# MAIN-SCH.net
KiCad netlist of a schematic drawn in Altium Designer
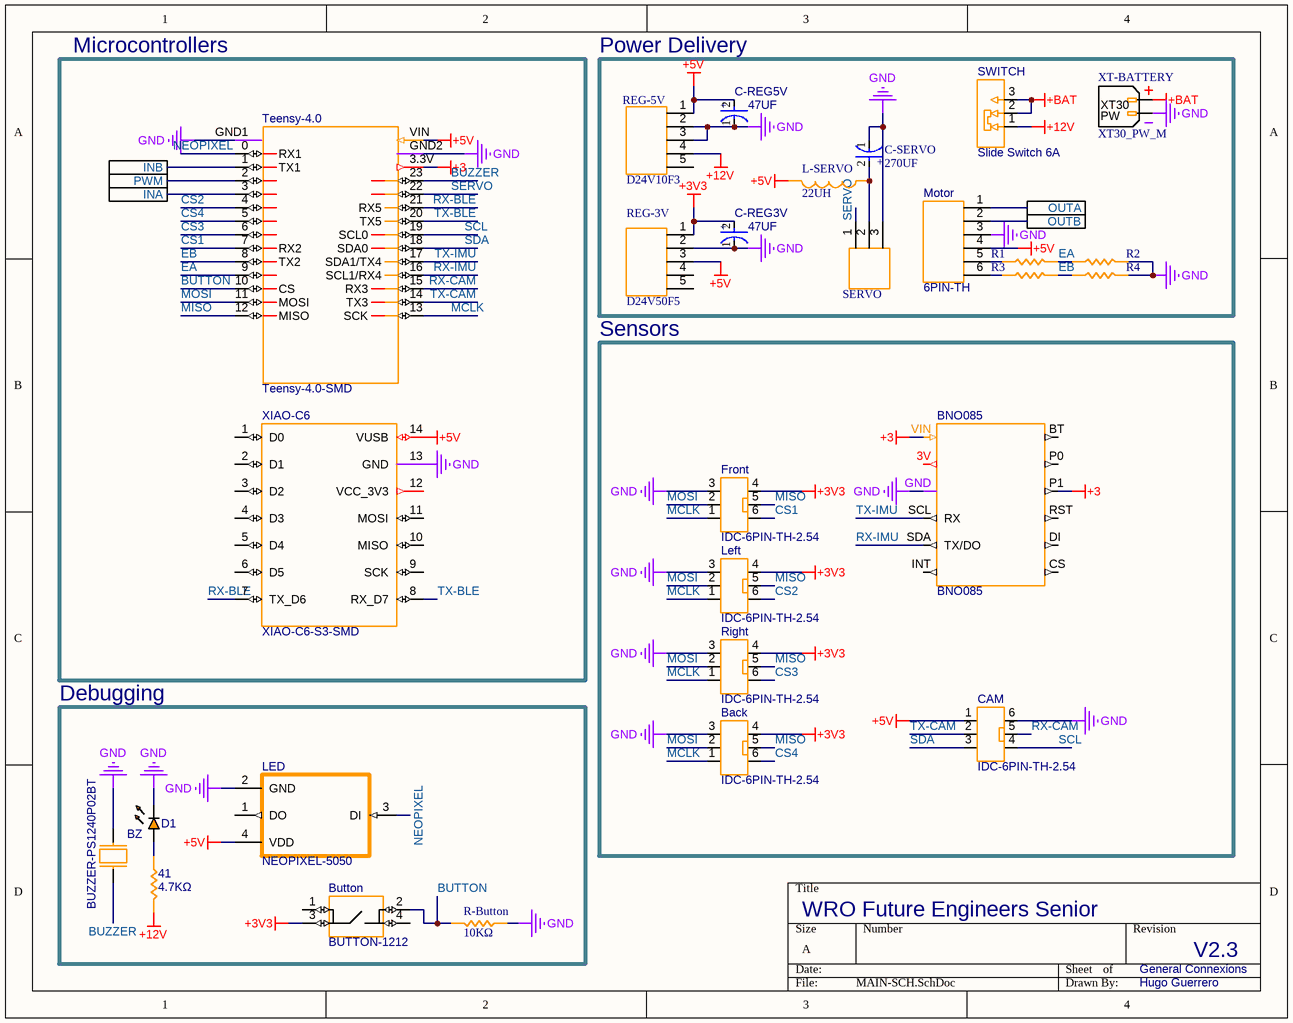
[diagram p0: MAIN-SCH.SchDoc]

(export (version "E")
  (design (tool "Eeschema 10.0.6"))
  (components
    (comp (ref "41")
      (value "4.7KΩ")
      (footprint "RES_0603")
      (description "Resistor SMD 0603 generic")
      (libsource (lib "GenericRC") (part "RES_0603"))
    )
    (comp (ref "Back")
      (value "IDC-6PIN-TH-2.54")
      (footprint "IDC-6PIN-TH-2.54")
      (libsource (lib "") (part "IDC-6PIN-TH-2.54_1"))
    )
    (comp (ref "BNO085") (value "BNO085") (footprint "BNO085") (libsource (lib "RC") (part "BNO085")))
    (comp (ref "Button") (value "BUTTON-1212") (footprint "BUTTON") (libsource (lib "RC") (part "BUTTON")))
    (comp (ref "BZ")
      (value "BUZZER-PS1240P02BT")
      (footprint "BUZZER")
      (libsource (lib "RC") (part "BUZZER-PS1240P02BT"))
    )
    (comp (ref "C-REG3V")
      (value "47UF")
      (footprint "FP-FTD8-MFG")
      (description "CAP ALUM 220UF 20% 25V SMD")
      (fields (field (name "TOLERANCE") "20%") (field (name "VOLTAGE") "25V"))
      (libsource (lib "Altium Content Vault") (part "cf48714ba7e38822c1575c7ec0b6d1f"))
    )
    (comp (ref "C-REG5V")
      (value "47UF")
      (footprint "FP-FTD8-MFG")
      (description "CAP ALUM 220UF 20% 25V SMD")
      (fields (field (name "TOLERANCE") "20%") (field (name "VOLTAGE") "25V"))
      (libsource (lib "Altium Content Vault") (part "cf48714ba7e38822c1575c7ec0b6d1f"))
    )
    (comp (ref "C-SERVO")
      (value "270UF")
      (footprint "FP-FTD8-MFG")
      (description "CAP ALUM 220UF 20% 25V SMD")
      (fields (field (name "TOLERANCE") "20%") (field (name "VOLTAGE") "25V"))
      (libsource (lib "Altium Content Vault") (part "cf48714ba7e38822c1575c7ec0b6d1f"))
    )
    (comp (ref "CAM")
      (value "IDC-6PIN-TH-2.54")
      (footprint "IDC-6PIN-TH-2.54")
      (libsource (lib "RC") (part "IDC-6PIN-TH-2.54"))
    )
    (comp (ref "D1")
      (value "LED_0603")
      (footprint "LED_0603")
      (libsource (lib "GenericRC") (part "LED_0603"))
    )
    (comp (ref "D24V10F3")
      (value "REG-5V")
      (footprint "5PIN-TH")
      (description "2.54 Header")
      (libsource (lib "RC") (part "5PIN-TH"))
    )
    (comp (ref "D24V50F5")
      (value "REG-3V")
      (footprint "5PIN-TH")
      (description "2.54 Header")
      (libsource (lib "RC") (part "5PIN-TH"))
    )
    (comp (ref "Front")
      (value "IDC-6PIN-TH-2.54")
      (footprint "IDC-6PIN-TH-2.54")
      (libsource (lib "") (part "IDC-6PIN-TH-2.54_1"))
    )
    (comp (ref "L-SERVO")
      (value "22UH")
      (footprint "WRO-INDUCTOR")
      (description "Voltage Boost Inductor")
      (libsource (lib "RC") (part "WRO-INDUCTOR"))
    )
    (comp (ref "LED")
      (value "NEOPIXEL-5050")
      (footprint "NEOPIXEL-5050")
      (libsource (lib "RC") (part "NEOPIXEL-5050"))
    )
    (comp (ref "Left")
      (value "IDC-6PIN-TH-2.54")
      (footprint "IDC-6PIN-TH-2.54")
      (libsource (lib "") (part "IDC-6PIN-TH-2.54_1"))
    )
    (comp (ref "Motor") (value "6PIN-TH") (footprint "6PIN-TH") (libsource (lib "RC") (part "6PIN-TH")))
    (comp (ref "R-Button")
      (value "10KΩ")
      (footprint "RES_0603")
      (description "Resistor SMD 0603 generic")
      (libsource (lib "RC") (part "RES_0603"))
    )
    (comp (ref "R1")
      (value "10KΩ")
      (footprint "RES_0603")
      (description "Resistor SMD 0603 generic")
      (libsource (lib "RC") (part "RES_0603"))
    )
    (comp (ref "R2")
      (value "10KΩ")
      (footprint "RES_0603")
      (description "Resistor SMD 0603 generic")
      (libsource (lib "RC") (part "RES_0603"))
    )
    (comp (ref "R3")
      (value "10KΩ")
      (footprint "RES_0603")
      (description "Resistor SMD 0603 generic")
      (libsource (lib "RC") (part "RES_0603"))
    )
    (comp (ref "R4")
      (value "10KΩ")
      (footprint "RES_0603")
      (description "Resistor SMD 0603 generic")
      (libsource (lib "RC") (part "RES_0603"))
    )
    (comp (ref "Right")
      (value "IDC-6PIN-TH-2.54")
      (footprint "IDC-6PIN-TH-2.54")
      (libsource (lib "") (part "IDC-6PIN-TH-2.54_1"))
    )
    (comp (ref "SERVO")
      (value "3PIN")
      (footprint "3PIN")
      (description "2.54 Header")
      (libsource (lib "RC") (part "3PIN"))
    )
    (comp (ref "SWITCH")
      (value "Slide Switch 6A")
      (footprint "Slide Switch 6A")
      (libsource (lib "RC") (part "Slide Switch 6A"))
    )
    (comp (ref "Teensy-4.0")
      (value "Teensy-4.0-SMD")
      (footprint "Teensy-4.0-SMD")
      (libsource (lib "RC") (part "Teensy-4.0-SMD"))
    )
    (comp (ref "XIAO-C6")
      (value "XIAO-C6-S3-SMD")
      (footprint "XIAO-C6-S3-SMD")
      (libsource (lib "RC") (part "XIAO-C6-S3-SMD"))
    )
    (comp (ref "XT-BATTERY")
      (value "XT30_PW_M")
      (footprint "XT30_PW_M")
      (libsource (lib "RC") (part "XT30_PW_M"))
    )
  )
  (nets
    (net (code "1") (name "+3") (class "Default")
      (node (ref "BNO085") (pin "P1") (pintype "output"))
      (node (ref "BNO085") (pin "VIN") (pintype "input"))
      (node (ref "Teensy-4.0") (pin "3.3V") (pinfunction "3.3V-2_3.3V") (pintype "output"))
    )
    (net (code "2") (name "+3V3") (class "Default")
      (node (ref "Back") (pin "4") (pintype "passive"))
      (node (ref "Button") (pin "3") (pinfunction "3_3") (pintype "bidirectional"))
      (node (ref "C-REG3V") (pin "2") (pinfunction "A_2") (pintype "passive"))
      (node (ref "D24V50F5") (pin "1") (pinfunction "01_1") (pintype "passive"))
      (node (ref "Front") (pin "4") (pintype "passive"))
      (node (ref "Left") (pin "4") (pintype "passive"))
      (node (ref "Right") (pin "4") (pintype "passive"))
    )
    (net (code "3") (name "+5V") (class "Default")
      (node (ref "C-REG5V") (pin "2") (pinfunction "A_2") (pintype "passive"))
      (node (ref "CAM") (pin "1") (pintype "passive"))
      (node (ref "D24V10F3") (pin "1") (pinfunction "01_1") (pintype "passive"))
      (node (ref "D24V50F5") (pin "3") (pinfunction "03_3") (pintype "passive"))
      (node (ref "L-SERVO") (pin "2") (pintype "passive"))
      (node (ref "LED") (pin "4") (pinfunction "VDD_4") (pintype "power_in"))
      (node (ref "Motor") (pin "4") (pinfunction "04_4") (pintype "passive"))
      (node (ref "Teensy-4.0") (pin "VIN") (pinfunction "VIN_VIN") (pintype "input"))
      (node (ref "XIAO-C6") (pin "14") (pinfunction "VUSB_14") (pintype "bidirectional"))
    )
    (net (code "4") (name "+12V") (class "Default")
      (node (ref "41") (pin "1") (pintype "passive"))
      (node (ref "D24V10F3") (pin "4") (pinfunction "04_4") (pintype "passive"))
      (node (ref "SWITCH") (pin "1") (pinfunction "NC_1") (pintype "passive"))
    )
    (net (code "5") (name "+BAT") (class "Default")
      (node (ref "SWITCH") (pin "2") (pinfunction "COM_2") (pintype "passive"))
      (node (ref "SWITCH") (pin "3") (pinfunction "NO_3") (pintype "passive"))
      (node (ref "XT-BATTERY") (pin "P") (pinfunction "P_P") (pintype "power_in"))
    )
    (net (code "6") (name "/BUTTON") (class "Default")
      (node (ref "Button") (pin "2") (pinfunction "2_2") (pintype "bidirectional"))
      (node (ref "R-Button") (pin "1") (pintype "passive"))
      (node (ref "Teensy-4.0") (pin "10") (pinfunction "CS_10") (pintype "bidirectional"))
    )
    (net (code "7") (name "/BUZZER") (class "Default")
      (node (ref "BZ") (pin "1") (pinfunction "1_1") (pintype "passive"))
      (node (ref "Teensy-4.0") (pin "23") (pinfunction "23_23") (pintype "bidirectional"))
    )
    (net (code "8") (name "/CS1") (class "Default")
      (node (ref "Front") (pin "6") (pintype "passive"))
      (node (ref "Teensy-4.0") (pin "7") (pinfunction "RX2_7") (pintype "bidirectional"))
    )
    (net (code "9") (name "/CS2") (class "Default")
      (node (ref "Left") (pin "6") (pintype "passive"))
      (node (ref "Teensy-4.0") (pin "4") (pinfunction "4_4") (pintype "bidirectional"))
    )
    (net (code "10") (name "/CS3") (class "Default")
      (node (ref "Right") (pin "6") (pintype "passive"))
      (node (ref "Teensy-4.0") (pin "6") (pinfunction "6_6") (pintype "bidirectional"))
    )
    (net (code "11") (name "/CS4") (class "Default")
      (node (ref "Back") (pin "6") (pintype "passive"))
      (node (ref "Teensy-4.0") (pin "5") (pinfunction "5_5") (pintype "bidirectional"))
    )
    (net (code "12") (name "/EA") (class "Default")
      (node (ref "R1") (pin "1") (pintype "passive"))
      (node (ref "R2") (pin "2") (pintype "passive"))
      (node (ref "Teensy-4.0") (pin "9") (pinfunction "9_9") (pintype "bidirectional"))
    )
    (net (code "13") (name "/EB") (class "Default")
      (node (ref "R3") (pin "1") (pintype "passive"))
      (node (ref "R4") (pin "2") (pintype "passive"))
      (node (ref "Teensy-4.0") (pin "8") (pinfunction "TX2_8") (pintype "bidirectional"))
    )
    (net (code "14") (name "/INA") (class "Default")
      (node (ref "Teensy-4.0") (pin "3") (pinfunction "3_3") (pintype "bidirectional"))
    )
    (net (code "15") (name "/INB") (class "Default")
      (node (ref "Teensy-4.0") (pin "1") (pinfunction "TX1_1") (pintype "bidirectional"))
    )
    (net (code "16") (name "/MCLK") (class "Default")
      (node (ref "Back") (pin "1") (pintype "passive"))
      (node (ref "Front") (pin "1") (pintype "passive"))
      (node (ref "Left") (pin "1") (pintype "passive"))
      (node (ref "Right") (pin "1") (pintype "passive"))
      (node (ref "Teensy-4.0") (pin "13") (pinfunction "SCK_13") (pintype "bidirectional"))
    )
    (net (code "17") (name "/MISO") (class "Default")
      (node (ref "Back") (pin "5") (pintype "passive"))
      (node (ref "Front") (pin "5") (pintype "passive"))
      (node (ref "Left") (pin "5") (pintype "passive"))
      (node (ref "Right") (pin "5") (pintype "passive"))
      (node (ref "Teensy-4.0") (pin "12") (pinfunction "MISO_12") (pintype "bidirectional"))
    )
    (net (code "18") (name "/MOSI") (class "Default")
      (node (ref "Back") (pin "2") (pintype "passive"))
      (node (ref "Front") (pin "2") (pintype "passive"))
      (node (ref "Left") (pin "2") (pintype "passive"))
      (node (ref "Right") (pin "2") (pintype "passive"))
      (node (ref "Teensy-4.0") (pin "11") (pinfunction "MOSI_11") (pintype "bidirectional"))
    )
    (net (code "19") (name "/NEOPIXEL") (class "Default")
      (node (ref "LED") (pin "3") (pinfunction "DI_3") (pintype "input"))
      (node (ref "Teensy-4.0") (pin "0") (pinfunction "RX1_0") (pintype "bidirectional"))
    )
    (net (code "20") (name "/OUTA") (class "Default")
      (node (ref "Motor") (pin "1") (pinfunction "01_1") (pintype "passive"))
    )
    (net (code "21") (name "/OUTB") (class "Default")
      (node (ref "Motor") (pin "2") (pinfunction "02_2") (pintype "passive"))
    )
    (net (code "22") (name "/PWM") (class "Default")
      (node (ref "Teensy-4.0") (pin "2") (pinfunction "2_2") (pintype "bidirectional"))
    )
    (net (code "23") (name "/RX-BLE") (class "Default")
      (node (ref "Teensy-4.0") (pin "21") (pinfunction "RX5_21") (pintype "bidirectional"))
      (node (ref "XIAO-C6") (pin "7") (pinfunction "TX_D6_7") (pintype "bidirectional"))
    )
    (net (code "24") (name "/RX-CAM") (class "Default")
      (node (ref "CAM") (pin "5") (pintype "passive"))
      (node (ref "Teensy-4.0") (pin "15") (pinfunction "RX3_15") (pintype "bidirectional"))
    )
    (net (code "25") (name "/RX-IMU") (class "Default")
      (node (ref "BNO085") (pin "SDA") (pinfunction "TX/DO_SDA") (pintype "output"))
      (node (ref "Teensy-4.0") (pin "16") (pinfunction "SCL1/RX4_16") (pintype "bidirectional"))
    )
    (net (code "26") (name "/SCL") (class "Default")
      (node (ref "CAM") (pin "4") (pintype "passive"))
      (node (ref "Teensy-4.0") (pin "19") (pinfunction "SCL0_19") (pintype "bidirectional"))
    )
    (net (code "27") (name "/SDA") (class "Default")
      (node (ref "CAM") (pin "3") (pintype "passive"))
      (node (ref "Teensy-4.0") (pin "18") (pinfunction "SDA0_18") (pintype "bidirectional"))
    )
    (net (code "28") (name "/SERVO") (class "Default")
      (node (ref "SERVO") (pin "1") (pinfunction "01_1") (pintype "passive"))
      (node (ref "Teensy-4.0") (pin "22") (pinfunction "22_22") (pintype "bidirectional"))
    )
    (net (code "29") (name "/TX-BLE") (class "Default")
      (node (ref "Teensy-4.0") (pin "20") (pinfunction "TX5_20") (pintype "bidirectional"))
      (node (ref "XIAO-C6") (pin "8") (pinfunction "RX_D7_8") (pintype "bidirectional"))
    )
    (net (code "30") (name "/TX-CAM") (class "Default")
      (node (ref "CAM") (pin "2") (pintype "passive"))
      (node (ref "Teensy-4.0") (pin "14") (pinfunction "TX3_14") (pintype "bidirectional"))
    )
    (net (code "31") (name "/TX-IMU") (class "Default")
      (node (ref "BNO085") (pin "SCL") (pinfunction "RX_SCL") (pintype "output"))
      (node (ref "Teensy-4.0") (pin "17") (pinfunction "SDA1/TX4_17") (pintype "bidirectional"))
    )
    (net (code "32") (name "GND") (class "Default")
      (node (ref "BNO085") (pin "GND") (pintype "passive"))
      (node (ref "BZ") (pin "2") (pinfunction "2_2") (pintype "passive"))
      (node (ref "Back") (pin "3") (pintype "passive"))
      (node (ref "C-REG3V") (pin "1") (pinfunction "C_1") (pintype "passive"))
      (node (ref "C-REG5V") (pin "1") (pinfunction "C_1") (pintype "passive"))
      (node (ref "C-SERVO") (pin "1") (pinfunction "C_1") (pintype "passive"))
      (node (ref "CAM") (pin "6") (pintype "passive"))
      (node (ref "D1") (pin "C") (pinfunction "1_C") (pintype "passive"))
      (node (ref "D24V10F3") (pin "2") (pinfunction "02_2") (pintype "passive"))
      (node (ref "D24V10F3") (pin "3") (pinfunction "03_3") (pintype "passive"))
      (node (ref "D24V50F5") (pin "2") (pinfunction "02_2") (pintype "passive"))
      (node (ref "Front") (pin "3") (pintype "passive"))
      (node (ref "LED") (pin "2") (pinfunction "GND_2") (pintype "power_in"))
      (node (ref "Left") (pin "3") (pintype "passive"))
      (node (ref "Motor") (pin "3") (pinfunction "03_3") (pintype "passive"))
      (node (ref "R-Button") (pin "2") (pintype "passive"))
      (node (ref "R2") (pin "1") (pintype "passive"))
      (node (ref "R4") (pin "1") (pintype "passive"))
      (node (ref "Right") (pin "3") (pintype "passive"))
      (node (ref "SERVO") (pin "3") (pinfunction "03_3") (pintype "passive"))
      (node (ref "Teensy-4.0") (pin "GND1") (pinfunction "GND1_GND1") (pintype "power_in"))
      (node (ref "Teensy-4.0") (pin "GND2") (pinfunction "GND3_GND2") (pintype "power_in"))
      (node (ref "XIAO-C6") (pin "13") (pinfunction "GND_13") (pintype "power_in"))
      (node (ref "XT-BATTERY") (pin "N") (pinfunction "N_N") (pintype "power_in"))
    )
    (net (code "33") (name "Net-(C-SERVO-A)") (class "Default")
      (node (ref "C-SERVO") (pin "2") (pinfunction "A_2") (pintype "passive"))
      (node (ref "L-SERVO") (pin "1") (pintype "passive"))
      (node (ref "SERVO") (pin "2") (pinfunction "02_2") (pintype "passive"))
    )
    (net (code "34") (name "Net-(D1-2)") (class "Default")
      (node (ref "41") (pin "2") (pintype "passive"))
      (node (ref "D1") (pin "A") (pinfunction "2_A") (pintype "passive"))
    )
    (net (code "35") (name "Net-(Motor-05)") (class "Default")
      (node (ref "Motor") (pin "5") (pinfunction "05_5") (pintype "passive"))
      (node (ref "R1") (pin "2") (pintype "passive"))
    )
    (net (code "36") (name "Net-(Motor-06)") (class "Default")
      (node (ref "Motor") (pin "6") (pinfunction "06_6") (pintype "passive"))
      (node (ref "R3") (pin "2") (pintype "passive"))
    )
    (net (code "37") (name "unconnected-(BNO085-Pad3V)") (class "Default")
      (node (ref "BNO085") (pin "3V") (pintype "output"))
    )
    (net (code "38") (name "unconnected-(BNO085-PadBT)") (class "Default")
      (node (ref "BNO085") (pin "BT") (pintype "output"))
    )
    (net (code "39") (name "unconnected-(BNO085-PadCS)") (class "Default")
      (node (ref "BNO085") (pin "CS") (pintype "output"))
    )
    (net (code "40") (name "unconnected-(BNO085-PadDI)") (class "Default")
      (node (ref "BNO085") (pin "DI") (pintype "output"))
    )
    (net (code "41") (name "unconnected-(BNO085-PadINT)") (class "Default")
      (node (ref "BNO085") (pin "INT") (pintype "output"))
    )
    (net (code "42") (name "unconnected-(BNO085-PadP0)") (class "Default")
      (node (ref "BNO085") (pin "P0") (pintype "output"))
    )
    (net (code "43") (name "unconnected-(BNO085-PadRST)") (class "Default")
      (node (ref "BNO085") (pin "RST") (pintype "output"))
    )
    (net (code "44") (name "unconnected-(Button-Pad1)") (class "Default")
      (node (ref "Button") (pin "1") (pinfunction "1_1") (pintype "bidirectional"))
    )
    (net (code "45") (name "unconnected-(Button-Pad4)") (class "Default")
      (node (ref "Button") (pin "4") (pinfunction "4_4") (pintype "bidirectional"))
    )
    (net (code "46") (name "unconnected-(D24V10F3-05-Pad5)") (class "Default")
      (node (ref "D24V10F3") (pin "5") (pinfunction "05_5") (pintype "passive"))
    )
    (net (code "47") (name "unconnected-(D24V50F5-04-Pad4)") (class "Default")
      (node (ref "D24V50F5") (pin "4") (pinfunction "04_4") (pintype "passive"))
    )
    (net (code "48") (name "unconnected-(D24V50F5-05-Pad5)") (class "Default")
      (node (ref "D24V50F5") (pin "5") (pinfunction "05_5") (pintype "passive"))
    )
    (net (code "49") (name "unconnected-(LED-DO-Pad1)") (class "Default")
      (node (ref "LED") (pin "1") (pinfunction "DO_1") (pintype "output"))
    )
    (net (code "50") (name "unconnected-(XIAO-C6-D0-Pad1)") (class "Default")
      (node (ref "XIAO-C6") (pin "1") (pinfunction "D0_1") (pintype "bidirectional"))
    )
    (net (code "51") (name "unconnected-(XIAO-C6-D1-Pad2)") (class "Default")
      (node (ref "XIAO-C6") (pin "2") (pinfunction "D1_2") (pintype "bidirectional"))
    )
    (net (code "52") (name "unconnected-(XIAO-C6-D2-Pad3)") (class "Default")
      (node (ref "XIAO-C6") (pin "3") (pinfunction "D2_3") (pintype "bidirectional"))
    )
    (net (code "53") (name "unconnected-(XIAO-C6-D3-Pad4)") (class "Default")
      (node (ref "XIAO-C6") (pin "4") (pinfunction "D3_4") (pintype "bidirectional"))
    )
    (net (code "54") (name "unconnected-(XIAO-C6-D4-Pad5)") (class "Default")
      (node (ref "XIAO-C6") (pin "5") (pinfunction "D4_5") (pintype "bidirectional"))
    )
    (net (code "55") (name "unconnected-(XIAO-C6-D5-Pad6)") (class "Default")
      (node (ref "XIAO-C6") (pin "6") (pinfunction "D5_6") (pintype "bidirectional"))
    )
    (net (code "56") (name "unconnected-(XIAO-C6-MISO-Pad10)") (class "Default")
      (node (ref "XIAO-C6") (pin "10") (pinfunction "MISO_10") (pintype "bidirectional"))
    )
    (net (code "57") (name "unconnected-(XIAO-C6-MOSI-Pad11)") (class "Default")
      (node (ref "XIAO-C6") (pin "11") (pinfunction "MOSI_11") (pintype "bidirectional"))
    )
    (net (code "58") (name "unconnected-(XIAO-C6-SCK-Pad9)") (class "Default")
      (node (ref "XIAO-C6") (pin "9") (pinfunction "SCK_9") (pintype "bidirectional"))
    )
    (net (code "59") (name "unconnected-(XIAO-C6-VCC_3V3-Pad12)") (class "Default")
      (node (ref "XIAO-C6") (pin "12") (pinfunction "VCC_3V3_12") (pintype "output"))
    )
  )
)
